# explorator_breakout_pcb_40mm_v1.net
KiCad netlist of a schematic drawn in EAGLE
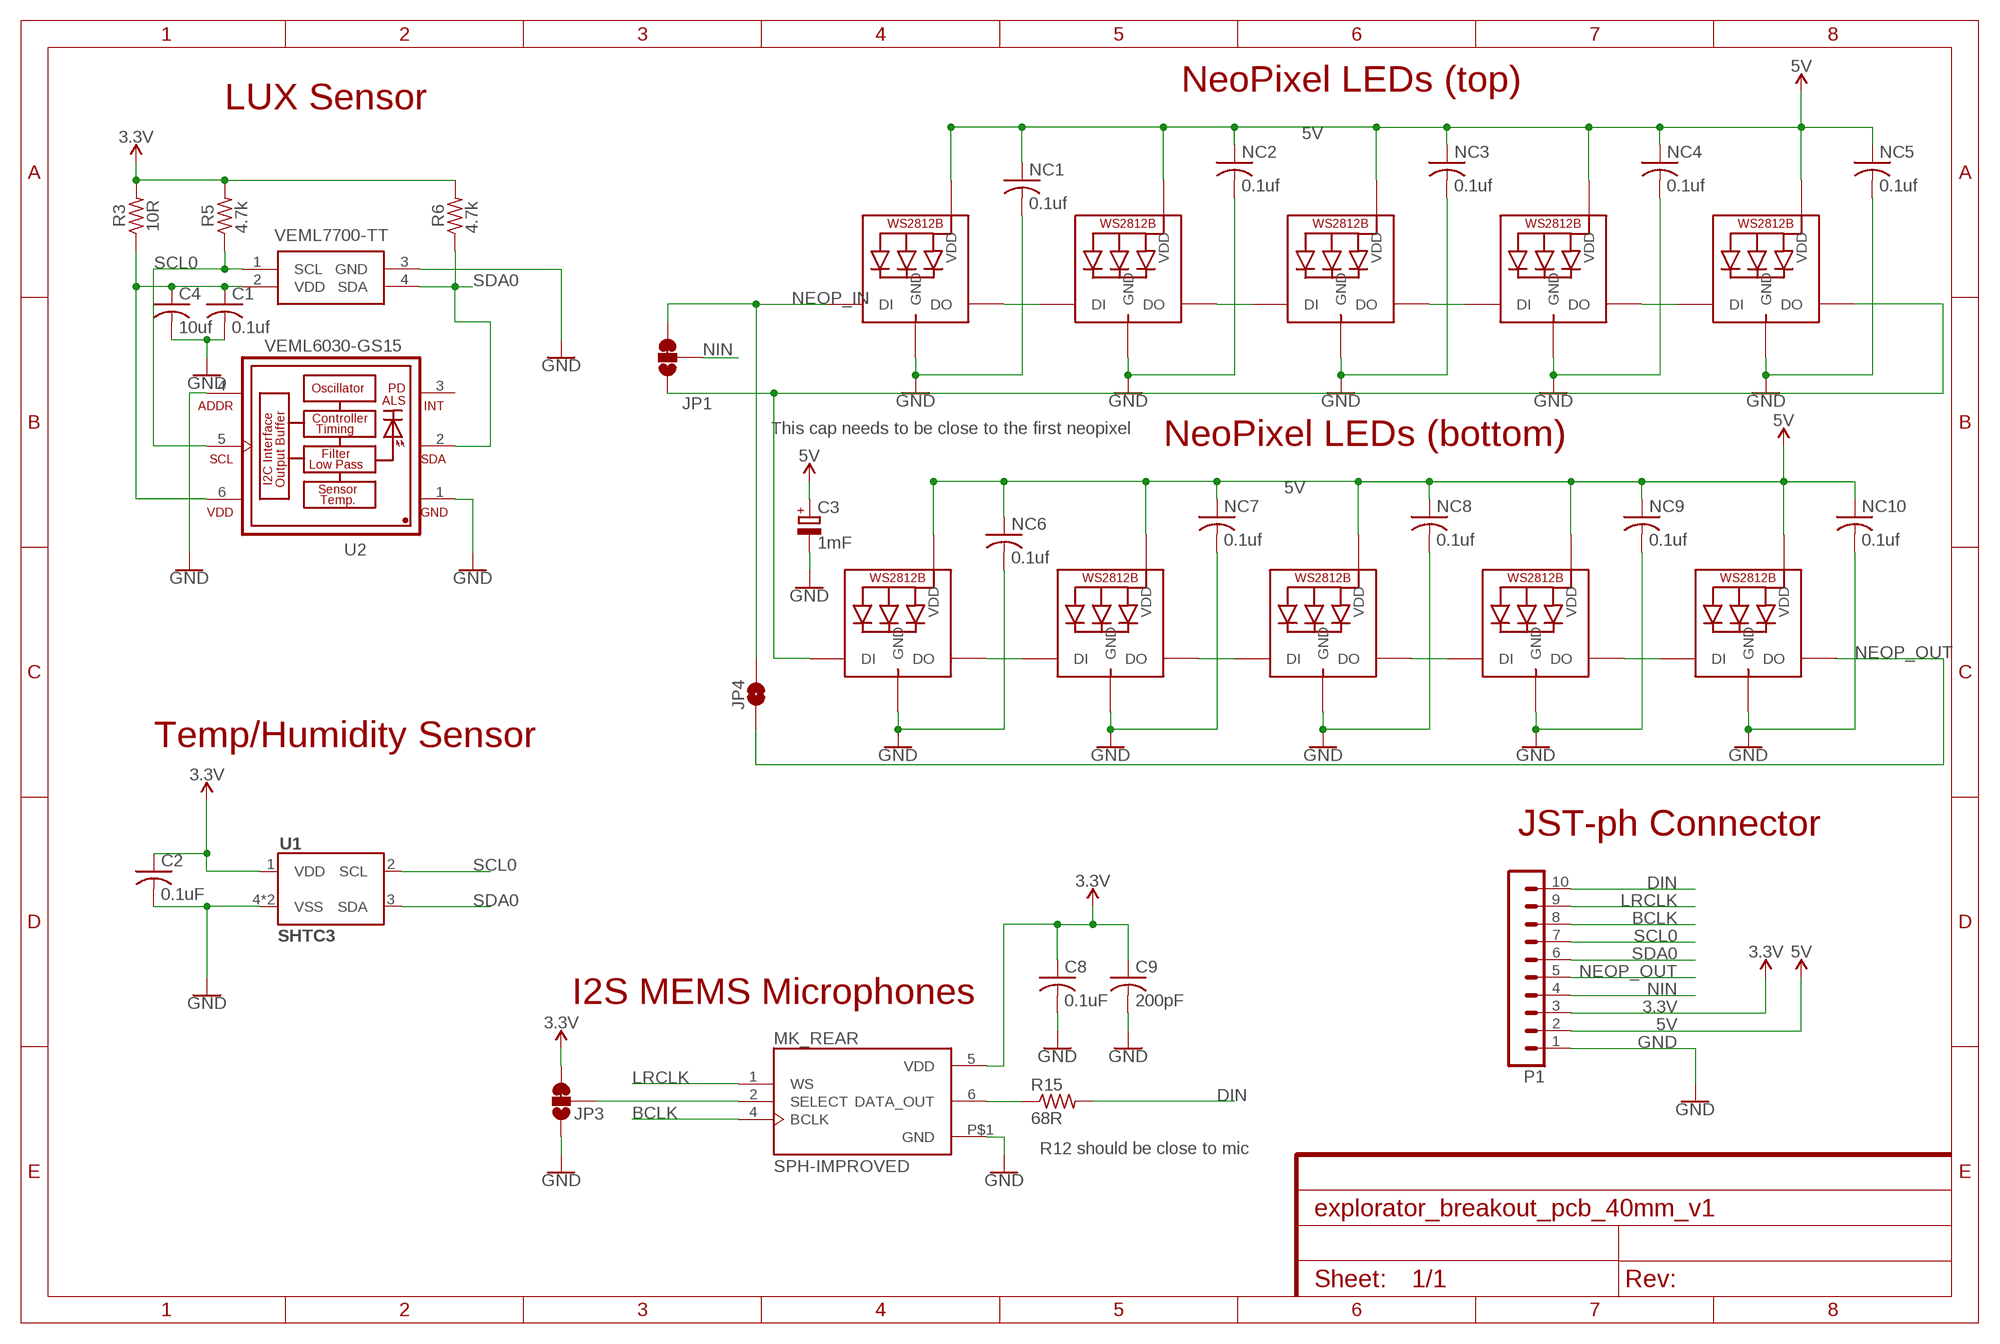
[diagram p0: schematic, sheet 1]

(export (version "E")
  (design (tool "Eeschema 10.0.6"))
  (components
    (comp (ref "C1")
      (value "0.1uf")
      (footprint "eagle-import:C0805")
      (libsource (lib "eagle-import") (part "C-USC0805"))
    )
    (comp (ref "C2")
      (value "0.1uF")
      (footprint "eagle-import:C0805")
      (libsource (lib "eagle-import") (part "C-USC0805"))
    )
    (comp (ref "C3")
      (value "1mF")
      (footprint "eagle-import:153CLV-1012")
      (libsource (lib "eagle-import") (part "CPOL-EU153CLV-1012"))
    )
    (comp (ref "C4")
      (value "10uf")
      (footprint "eagle-import:C0805")
      (libsource (lib "eagle-import") (part "C-USC0805"))
    )
    (comp (ref "C8")
      (value "0.1uF")
      (footprint "eagle-import:C0805")
      (libsource (lib "eagle-import") (part "C-USC0805"))
    )
    (comp (ref "C9")
      (value "200pF")
      (footprint "eagle-import:C0805")
      (libsource (lib "eagle-import") (part "C-USC0805"))
    )
    (comp (ref "JP1")
      (value "JUMPER-SMT_3_1-NC_TRACE_SILK")
      (footprint "eagle-import:SMT-JUMPER_3_1-NC_TRACE_SILK")
      (libsource (lib "eagle-import") (part "JUMPER-SMT_3_1-NC_TRACE_SILK"))
    )
    (comp (ref "JP3")
      (value "JUMPER-SMT_3_1-NC_TRACE_SILK")
      (footprint "eagle-import:SMT-JUMPER_3_1-NC_TRACE_SILK")
      (libsource (lib "eagle-import") (part "JUMPER-SMT_3_1-NC_TRACE_SILK"))
    )
    (comp (ref "JP4")
      (value "JUMPER-SMT_2_NO_SILK")
      (footprint "eagle-import:SMT-JUMPER_2_NO_SILK")
      (libsource (lib "eagle-import") (part "JUMPER-SMT_2_NO_SILK"))
    )
    (comp (ref "MK_REAR")
      (value "SPH-IMPROVED")
      (footprint "eagle-import:MIC_SPH0645LM4H-B_LARGER_RING")
      (libsource (lib "eagle-import") (part "SPH-IMPROVED"))
    )
    (comp (ref "NC1")
      (value "0.1uf")
      (footprint "eagle-import:C0805")
      (libsource (lib "eagle-import") (part "C-USC0805"))
    )
    (comp (ref "NC2")
      (value "0.1uf")
      (footprint "eagle-import:C0805")
      (libsource (lib "eagle-import") (part "C-USC0805"))
    )
    (comp (ref "NC3")
      (value "0.1uf")
      (footprint "eagle-import:C0805")
      (libsource (lib "eagle-import") (part "C-USC0805"))
    )
    (comp (ref "NC4")
      (value "0.1uf")
      (footprint "eagle-import:C0805")
      (libsource (lib "eagle-import") (part "C-USC0805"))
    )
    (comp (ref "NC5")
      (value "0.1uf")
      (footprint "eagle-import:C0805")
      (libsource (lib "eagle-import") (part "C-USC0805"))
    )
    (comp (ref "NC6")
      (value "0.1uf")
      (footprint "eagle-import:C0805")
      (libsource (lib "eagle-import") (part "C-USC0805"))
    )
    (comp (ref "NC7")
      (value "0.1uf")
      (footprint "eagle-import:C0805")
      (libsource (lib "eagle-import") (part "C-USC0805"))
    )
    (comp (ref "NC8")
      (value "0.1uf")
      (footprint "eagle-import:C0805")
      (libsource (lib "eagle-import") (part "C-USC0805"))
    )
    (comp (ref "NC9")
      (value "0.1uf")
      (footprint "eagle-import:C0805")
      (libsource (lib "eagle-import") (part "C-USC0805"))
    )
    (comp (ref "NC10")
      (value "0.1uf")
      (footprint "eagle-import:C0805")
      (libsource (lib "eagle-import") (part "C-USC0805"))
    )
    (comp (ref "NEO_01")
      (value "WS2812")
      (footprint "eagle-import:WS2812B")
      (libsource (lib "eagle-import") (part "WS2812"))
    )
    (comp (ref "NEO_02")
      (value "WS2812")
      (footprint "eagle-import:WS2812B")
      (libsource (lib "eagle-import") (part "WS2812"))
    )
    (comp (ref "NEO_03")
      (value "WS2812")
      (footprint "eagle-import:WS2812B")
      (libsource (lib "eagle-import") (part "WS2812"))
    )
    (comp (ref "NEO_04")
      (value "WS2812")
      (footprint "eagle-import:WS2812B")
      (libsource (lib "eagle-import") (part "WS2812"))
    )
    (comp (ref "NEO_05")
      (value "WS2812")
      (footprint "eagle-import:WS2812B")
      (libsource (lib "eagle-import") (part "WS2812"))
    )
    (comp (ref "NEO_06")
      (value "WS2812")
      (footprint "eagle-import:WS2812B")
      (libsource (lib "eagle-import") (part "WS2812"))
    )
    (comp (ref "NEO_07")
      (value "WS2812")
      (footprint "eagle-import:WS2812B")
      (libsource (lib "eagle-import") (part "WS2812"))
    )
    (comp (ref "NEO_08")
      (value "WS2812")
      (footprint "eagle-import:WS2812B")
      (libsource (lib "eagle-import") (part "WS2812"))
    )
    (comp (ref "NEO_09")
      (value "WS2812")
      (footprint "eagle-import:WS2812B")
      (libsource (lib "eagle-import") (part "WS2812"))
    )
    (comp (ref "NEO_10")
      (value "WS2812")
      (footprint "eagle-import:WS2812B")
      (libsource (lib "eagle-import") (part "WS2812"))
    )
    (comp (ref "P1")
      (value "B10B-PH-K")
      (footprint "eagle-import:B10B-PH-K")
      (libsource (lib "eagle-import") (part "B10B-PH-K"))
    )
    (comp (ref "R3")
      (value "10R")
      (footprint "eagle-import:R0805")
      (libsource (lib "eagle-import") (part "R-US_R0805"))
    )
    (comp (ref "R5")
      (value "4.7k")
      (footprint "eagle-import:R0805")
      (libsource (lib "eagle-import") (part "R-US_R0805"))
    )
    (comp (ref "R6")
      (value "4.7k")
      (footprint "eagle-import:R0805")
      (libsource (lib "eagle-import") (part "R-US_R0805"))
    )
    (comp (ref "R15")
      (value "68R")
      (footprint "eagle-import:R0805")
      (libsource (lib "eagle-import") (part "R-US_R0805"))
    )
    (comp (ref "U1")
      (value "SHTC3")
      (footprint "eagle-import:SHTC3")
      (libsource (lib "eagle-import") (part "SHTC3"))
    )
    (comp (ref "U2")
      (value "VEML6030-GS15")
      (footprint "eagle-import:VISHAY_VEML6030_2X2X0.87")
      (fields (field (name "MF") "Vishay Semiconductor"))
      (libsource (lib "eagle-import") (part "VEML6030-GS15"))
    )
    (comp (ref "VEML_F")
      (value "VEML7700-TT")
      (footprint "eagle-import:VEML7700")
      (fields (field (name "MOUSER_PART_NUMBER") "78-VEML7700-TT") (field (name "RS_PART_NUMBER") "1226791P"))
      (libsource (lib "eagle-import") (part "VEML7700-TT"))
    )
  )
  (nets
    (net (code "1") (name "/BCLK") (class "Default")
      (node (ref "MK_REAR") (pin "4") (pinfunction "BCLK_4") (pintype "input"))
      (node (ref "P1") (pin "8") (pinfunction "8_8") (pintype "passive"))
    )
    (net (code "2") (name "/DIN") (class "Default")
      (node (ref "P1") (pin "10") (pinfunction "10_10") (pintype "passive"))
      (node (ref "R15") (pin "2") (pinfunction "2_2") (pintype "passive"))
    )
    (net (code "3") (name "/LRCLK") (class "Default")
      (node (ref "MK_REAR") (pin "1") (pinfunction "WS_1") (pintype "input"))
      (node (ref "P1") (pin "9") (pinfunction "9_9") (pintype "passive"))
    )
    (net (code "4") (name "/NEOP_IN") (class "Default")
      (node (ref "JP1") (pin "3") (pinfunction "3_3") (pintype "passive"))
      (node (ref "JP4") (pin "2") (pinfunction "2_2") (pintype "passive"))
      (node (ref "NEO_01") (pin "4-DIN") (pinfunction "DI_4-DIN") (pintype "input"))
    )
    (net (code "5") (name "/NEOP_OUT") (class "Default")
      (node (ref "JP4") (pin "1") (pinfunction "1_1") (pintype "passive"))
      (node (ref "NEO_10") (pin "2-DOUT") (pinfunction "DO_2-DOUT") (pintype "output"))
      (node (ref "P1") (pin "5") (pinfunction "5_5") (pintype "passive"))
    )
    (net (code "6") (name "/NIN") (class "Default")
      (node (ref "JP1") (pin "2") (pinfunction "2_2") (pintype "passive"))
      (node (ref "P1") (pin "4") (pinfunction "4_4") (pintype "passive"))
    )
    (net (code "7") (name "/SCL0") (class "Default")
      (node (ref "P1") (pin "7") (pinfunction "7_7") (pintype "passive"))
      (node (ref "R5") (pin "1") (pinfunction "1_1") (pintype "passive"))
      (node (ref "U1") (pin "2") (pinfunction "SCL_2") (pintype "bidirectional"))
      (node (ref "U2") (pin "5") (pinfunction "SCL_5") (pintype "input"))
      (node (ref "VEML_F") (pin "1") (pinfunction "SCL_1") (pintype "bidirectional"))
    )
    (net (code "8") (name "/SDA0") (class "Default")
      (node (ref "P1") (pin "6") (pinfunction "6_6") (pintype "passive"))
      (node (ref "R6") (pin "1") (pinfunction "1_1") (pintype "passive"))
      (node (ref "U1") (pin "3") (pinfunction "SDA_3") (pintype "bidirectional"))
      (node (ref "U2") (pin "2") (pinfunction "SDA_2") (pintype "bidirectional"))
      (node (ref "VEML_F") (pin "4") (pinfunction "SDA_4") (pintype "bidirectional"))
    )
    (net (code "9") (name "3.3V") (class "Default")
      (node (ref "C2") (pin "1") (pinfunction "1_1") (pintype "passive"))
      (node (ref "C8") (pin "1") (pinfunction "1_1") (pintype "passive"))
      (node (ref "C9") (pin "1") (pinfunction "1_1") (pintype "passive"))
      (node (ref "JP3") (pin "3") (pinfunction "3_3") (pintype "passive"))
      (node (ref "MK_REAR") (pin "5") (pinfunction "VDD_5") (pintype "power_in"))
      (node (ref "P1") (pin "3") (pinfunction "3_3") (pintype "passive"))
      (node (ref "R3") (pin "2") (pinfunction "2_2") (pintype "passive"))
      (node (ref "R5") (pin "2") (pinfunction "2_2") (pintype "passive"))
      (node (ref "R6") (pin "2") (pinfunction "2_2") (pintype "passive"))
      (node (ref "U1") (pin "1") (pinfunction "VDD_1") (pintype "bidirectional"))
    )
    (net (code "10") (name "5V") (class "Default")
      (node (ref "C3") (pin "+") (pinfunction "+_+") (pintype "passive"))
      (node (ref "NC1") (pin "1") (pinfunction "1_1") (pintype "passive"))
      (node (ref "NC10") (pin "1") (pinfunction "1_1") (pintype "passive"))
      (node (ref "NC2") (pin "1") (pinfunction "1_1") (pintype "passive"))
      (node (ref "NC3") (pin "1") (pinfunction "1_1") (pintype "passive"))
      (node (ref "NC4") (pin "1") (pinfunction "1_1") (pintype "passive"))
      (node (ref "NC5") (pin "1") (pinfunction "1_1") (pintype "passive"))
      (node (ref "NC6") (pin "1") (pinfunction "1_1") (pintype "passive"))
      (node (ref "NC7") (pin "1") (pinfunction "1_1") (pintype "passive"))
      (node (ref "NC8") (pin "1") (pinfunction "1_1") (pintype "passive"))
      (node (ref "NC9") (pin "1") (pinfunction "1_1") (pintype "passive"))
      (node (ref "NEO_01") (pin "1-VDD") (pinfunction "VDD_1-VDD") (pintype "power_in"))
      (node (ref "NEO_02") (pin "1-VDD") (pinfunction "VDD_1-VDD") (pintype "power_in"))
      (node (ref "NEO_03") (pin "1-VDD") (pinfunction "VDD_1-VDD") (pintype "power_in"))
      (node (ref "NEO_04") (pin "1-VDD") (pinfunction "VDD_1-VDD") (pintype "power_in"))
      (node (ref "NEO_05") (pin "1-VDD") (pinfunction "VDD_1-VDD") (pintype "power_in"))
      (node (ref "NEO_06") (pin "1-VDD") (pinfunction "VDD_1-VDD") (pintype "power_in"))
      (node (ref "NEO_07") (pin "1-VDD") (pinfunction "VDD_1-VDD") (pintype "power_in"))
      (node (ref "NEO_08") (pin "1-VDD") (pinfunction "VDD_1-VDD") (pintype "power_in"))
      (node (ref "NEO_09") (pin "1-VDD") (pinfunction "VDD_1-VDD") (pintype "power_in"))
      (node (ref "NEO_10") (pin "1-VDD") (pinfunction "VDD_1-VDD") (pintype "power_in"))
      (node (ref "P1") (pin "2") (pinfunction "2_2") (pintype "passive"))
    )
    (net (code "11") (name "GND") (class "Default")
      (node (ref "C1") (pin "2") (pinfunction "2_2") (pintype "passive"))
      (node (ref "C2") (pin "2") (pinfunction "2_2") (pintype "passive"))
      (node (ref "C3") (pin "-") (pinfunction "-_-") (pintype "passive"))
      (node (ref "C4") (pin "2") (pinfunction "2_2") (pintype "passive"))
      (node (ref "C8") (pin "2") (pinfunction "2_2") (pintype "passive"))
      (node (ref "C9") (pin "2") (pinfunction "2_2") (pintype "passive"))
      (node (ref "JP3") (pin "1") (pinfunction "1_1") (pintype "passive"))
      (node (ref "MK_REAR") (pin "P$1") (pinfunction "GND_P$1") (pintype "power_in"))
      (node (ref "NC1") (pin "2") (pinfunction "2_2") (pintype "passive"))
      (node (ref "NC10") (pin "2") (pinfunction "2_2") (pintype "passive"))
      (node (ref "NC2") (pin "2") (pinfunction "2_2") (pintype "passive"))
      (node (ref "NC3") (pin "2") (pinfunction "2_2") (pintype "passive"))
      (node (ref "NC4") (pin "2") (pinfunction "2_2") (pintype "passive"))
      (node (ref "NC5") (pin "2") (pinfunction "2_2") (pintype "passive"))
      (node (ref "NC6") (pin "2") (pinfunction "2_2") (pintype "passive"))
      (node (ref "NC7") (pin "2") (pinfunction "2_2") (pintype "passive"))
      (node (ref "NC8") (pin "2") (pinfunction "2_2") (pintype "passive"))
      (node (ref "NC9") (pin "2") (pinfunction "2_2") (pintype "passive"))
      (node (ref "NEO_01") (pin "3-GND") (pinfunction "GND_3-GND") (pintype "power_in"))
      (node (ref "NEO_02") (pin "3-GND") (pinfunction "GND_3-GND") (pintype "power_in"))
      (node (ref "NEO_03") (pin "3-GND") (pinfunction "GND_3-GND") (pintype "power_in"))
      (node (ref "NEO_04") (pin "3-GND") (pinfunction "GND_3-GND") (pintype "power_in"))
      (node (ref "NEO_05") (pin "3-GND") (pinfunction "GND_3-GND") (pintype "power_in"))
      (node (ref "NEO_06") (pin "3-GND") (pinfunction "GND_3-GND") (pintype "power_in"))
      (node (ref "NEO_07") (pin "3-GND") (pinfunction "GND_3-GND") (pintype "power_in"))
      (node (ref "NEO_08") (pin "3-GND") (pinfunction "GND_3-GND") (pintype "power_in"))
      (node (ref "NEO_09") (pin "3-GND") (pinfunction "GND_3-GND") (pintype "power_in"))
      (node (ref "NEO_10") (pin "3-GND") (pinfunction "GND_3-GND") (pintype "power_in"))
      (node (ref "P1") (pin "1") (pinfunction "1_1") (pintype "passive"))
      (node (ref "U1") (pin "4") (pinfunction "VSS_4") (pintype "bidirectional"))
      (node (ref "U1") (pin "5") (pinfunction "VSS_5") (pintype "bidirectional"))
      (node (ref "U2") (pin "1") (pinfunction "GND_1") (pintype "power_in"))
      (node (ref "U2") (pin "4") (pinfunction "ADDR_4") (pintype "bidirectional"))
      (node (ref "VEML_F") (pin "3") (pinfunction "GND_3") (pintype "bidirectional"))
    )
    (net (code "12") (name "Net-(MK_REAR-DATA_OUT)") (class "Default")
      (node (ref "MK_REAR") (pin "6") (pinfunction "DATA_OUT_6") (pintype "output"))
      (node (ref "R15") (pin "1") (pinfunction "1_1") (pintype "passive"))
    )
    (net (code "13") (name "Net-(MK_REAR-SELECT)") (class "Default")
      (node (ref "JP3") (pin "2") (pinfunction "2_2") (pintype "passive"))
      (node (ref "MK_REAR") (pin "2") (pinfunction "SELECT_2") (pintype "input"))
    )
    (net (code "14") (name "Net-(NEO_01-DO)") (class "Default")
      (node (ref "NEO_01") (pin "2-DOUT") (pinfunction "DO_2-DOUT") (pintype "output"))
      (node (ref "NEO_02") (pin "4-DIN") (pinfunction "DI_4-DIN") (pintype "input"))
    )
    (net (code "15") (name "Net-(NEO_02-DO)") (class "Default")
      (node (ref "NEO_02") (pin "2-DOUT") (pinfunction "DO_2-DOUT") (pintype "output"))
      (node (ref "NEO_03") (pin "4-DIN") (pinfunction "DI_4-DIN") (pintype "input"))
    )
    (net (code "16") (name "Net-(NEO_03-DO)") (class "Default")
      (node (ref "NEO_03") (pin "2-DOUT") (pinfunction "DO_2-DOUT") (pintype "output"))
      (node (ref "NEO_04") (pin "4-DIN") (pinfunction "DI_4-DIN") (pintype "input"))
    )
    (net (code "17") (name "Net-(NEO_04-DO)") (class "Default")
      (node (ref "NEO_04") (pin "2-DOUT") (pinfunction "DO_2-DOUT") (pintype "output"))
      (node (ref "NEO_05") (pin "4-DIN") (pinfunction "DI_4-DIN") (pintype "input"))
    )
    (net (code "18") (name "Net-(NEO_05-DO)") (class "Default")
      (node (ref "JP1") (pin "1") (pinfunction "1_1") (pintype "passive"))
      (node (ref "NEO_05") (pin "2-DOUT") (pinfunction "DO_2-DOUT") (pintype "output"))
      (node (ref "NEO_06") (pin "4-DIN") (pinfunction "DI_4-DIN") (pintype "input"))
    )
    (net (code "19") (name "Net-(NEO_06-DO)") (class "Default")
      (node (ref "NEO_06") (pin "2-DOUT") (pinfunction "DO_2-DOUT") (pintype "output"))
      (node (ref "NEO_07") (pin "4-DIN") (pinfunction "DI_4-DIN") (pintype "input"))
    )
    (net (code "20") (name "Net-(NEO_07-DO)") (class "Default")
      (node (ref "NEO_07") (pin "2-DOUT") (pinfunction "DO_2-DOUT") (pintype "output"))
      (node (ref "NEO_08") (pin "4-DIN") (pinfunction "DI_4-DIN") (pintype "input"))
    )
    (net (code "21") (name "Net-(NEO_08-DO)") (class "Default")
      (node (ref "NEO_08") (pin "2-DOUT") (pinfunction "DO_2-DOUT") (pintype "output"))
      (node (ref "NEO_09") (pin "4-DIN") (pinfunction "DI_4-DIN") (pintype "input"))
    )
    (net (code "22") (name "Net-(NEO_09-DO)") (class "Default")
      (node (ref "NEO_09") (pin "2-DOUT") (pinfunction "DO_2-DOUT") (pintype "output"))
      (node (ref "NEO_10") (pin "4-DIN") (pinfunction "DI_4-DIN") (pintype "input"))
    )
    (net (code "23") (name "Net-(U2-VDD)") (class "Default")
      (node (ref "C1") (pin "1") (pinfunction "1_1") (pintype "passive"))
      (node (ref "C4") (pin "1") (pinfunction "1_1") (pintype "passive"))
      (node (ref "R3") (pin "1") (pinfunction "1_1") (pintype "passive"))
      (node (ref "U2") (pin "6") (pinfunction "VDD_6") (pintype "power_in"))
      (node (ref "VEML_F") (pin "2") (pinfunction "VDD_2") (pintype "bidirectional"))
    )
    (net (code "24") (name "unconnected-(U2-INT-Pad3)") (class "Default")
      (node (ref "U2") (pin "3") (pinfunction "INT_3") (pintype "output"))
    )
  )
)
